# SAS_UFL_Adapter.net
KiCad netlist of a schematic drawn in Altium Designer
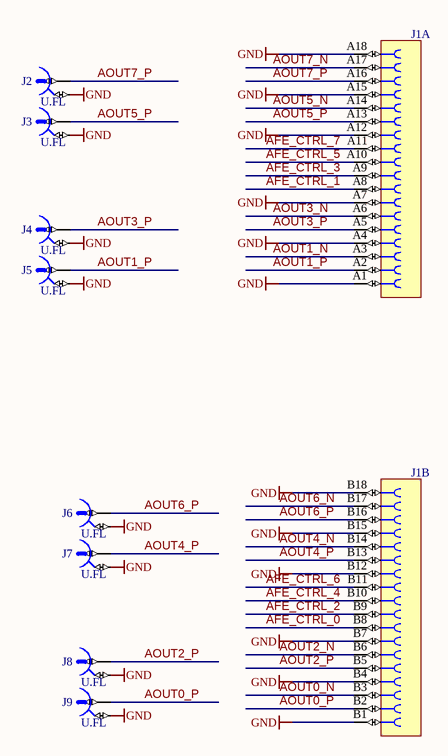
[diagram p0: SAS_UFL_Adapter.SchDoc]

(export (version "E")
  (design (tool "Eeschema 10.0.6"))
  (components
    (comp (ref "J1")
      (value "mini-SAS")
      (footprint "mini_SAS_PCB_EDGE")
      (description "36 Position mini-SAS PCB Edge Connector 36 (2x18)")
      (fields
        (field (name "PART NUMBER") "mini_SAS_PCB_EDGE")
        (field (name "MANUFACTURER") "PCB")
        (field (name "AUTHOR") "GK")
      )
      (libsource (lib "Connectors") (part "CON_mini_SAS_PCB_EDGE"))
    )
    (comp (ref "J2")
      (value "U.FL")
      (footprint "HIROSE_U.FL-R-SMT-1(10)")
      (fields
        (field (name "PART NUMBER") "HIROSE_U.FL-R-SMT-1(10)")
        (field (name "MANUFACTURER") "HIROSE (HRS)")
        (field (name "MANUFACTURER PART NUMBER") "U.FL-R-SMT-1(10)")
        (field (name "AUTHOR") "CERN DEM JLC")
      )
      (libsource (lib "Connectors") (part "Coax_1Male_1Shield"))
    )
    (comp (ref "J3")
      (value "U.FL")
      (footprint "HIROSE_U.FL-R-SMT-1(10)")
      (fields
        (field (name "PART NUMBER") "HIROSE_U.FL-R-SMT-1(10)")
        (field (name "MANUFACTURER") "HIROSE (HRS)")
        (field (name "MANUFACTURER PART NUMBER") "U.FL-R-SMT-1(10)")
        (field (name "AUTHOR") "CERN DEM JLC")
      )
      (libsource (lib "Connectors") (part "Coax_1Male_1Shield"))
    )
    (comp (ref "J4")
      (value "U.FL")
      (footprint "HIROSE_U.FL-R-SMT-1(10)")
      (fields
        (field (name "PART NUMBER") "HIROSE_U.FL-R-SMT-1(10)")
        (field (name "MANUFACTURER") "HIROSE (HRS)")
        (field (name "MANUFACTURER PART NUMBER") "U.FL-R-SMT-1(10)")
        (field (name "AUTHOR") "CERN DEM JLC")
      )
      (libsource (lib "Connectors") (part "Coax_1Male_1Shield"))
    )
    (comp (ref "J5")
      (value "U.FL")
      (footprint "HIROSE_U.FL-R-SMT-1(10)")
      (fields
        (field (name "PART NUMBER") "HIROSE_U.FL-R-SMT-1(10)")
        (field (name "MANUFACTURER") "HIROSE (HRS)")
        (field (name "MANUFACTURER PART NUMBER") "U.FL-R-SMT-1(10)")
        (field (name "AUTHOR") "CERN DEM JLC")
      )
      (libsource (lib "Connectors") (part "Coax_1Male_1Shield"))
    )
    (comp (ref "J6")
      (value "U.FL")
      (footprint "HIROSE_U.FL-R-SMT-1(10)")
      (fields
        (field (name "PART NUMBER") "HIROSE_U.FL-R-SMT-1(10)")
        (field (name "MANUFACTURER") "HIROSE (HRS)")
        (field (name "MANUFACTURER PART NUMBER") "U.FL-R-SMT-1(10)")
        (field (name "AUTHOR") "CERN DEM JLC")
      )
      (libsource (lib "Connectors") (part "Coax_1Male_1Shield"))
    )
    (comp (ref "J7")
      (value "U.FL")
      (footprint "HIROSE_U.FL-R-SMT-1(10)")
      (fields
        (field (name "PART NUMBER") "HIROSE_U.FL-R-SMT-1(10)")
        (field (name "MANUFACTURER") "HIROSE (HRS)")
        (field (name "MANUFACTURER PART NUMBER") "U.FL-R-SMT-1(10)")
        (field (name "AUTHOR") "CERN DEM JLC")
      )
      (libsource (lib "Connectors") (part "Coax_1Male_1Shield"))
    )
    (comp (ref "J8")
      (value "U.FL")
      (footprint "HIROSE_U.FL-R-SMT-1(10)")
      (fields
        (field (name "PART NUMBER") "HIROSE_U.FL-R-SMT-1(10)")
        (field (name "MANUFACTURER") "HIROSE (HRS)")
        (field (name "MANUFACTURER PART NUMBER") "U.FL-R-SMT-1(10)")
        (field (name "AUTHOR") "CERN DEM JLC")
      )
      (libsource (lib "Connectors") (part "Coax_1Male_1Shield"))
    )
    (comp (ref "J9")
      (value "U.FL")
      (footprint "HIROSE_U.FL-R-SMT-1(10)")
      (fields
        (field (name "PART NUMBER") "HIROSE_U.FL-R-SMT-1(10)")
        (field (name "MANUFACTURER") "HIROSE (HRS)")
        (field (name "MANUFACTURER PART NUMBER") "U.FL-R-SMT-1(10)")
        (field (name "AUTHOR") "CERN DEM JLC")
      )
      (libsource (lib "Connectors") (part "Coax_1Male_1Shield"))
    )
  )
  (nets
    (net (code "1") (name "/AFE_CTRL_0") (class "Default")
      (node (ref "J1") (pin "B8") (pinfunction "B8_B8") (pintype "bidirectional"))
    )
    (net (code "2") (name "/AFE_CTRL_1") (class "Default")
      (node (ref "J1") (pin "A8") (pinfunction "A8_A8") (pintype "bidirectional"))
    )
    (net (code "3") (name "/AFE_CTRL_2") (class "Default")
      (node (ref "J1") (pin "B9") (pinfunction "B9_B9") (pintype "bidirectional"))
    )
    (net (code "4") (name "/AFE_CTRL_3") (class "Default")
      (node (ref "J1") (pin "A9") (pinfunction "A9_A9") (pintype "bidirectional"))
    )
    (net (code "5") (name "/AFE_CTRL_4") (class "Default")
      (node (ref "J1") (pin "B10") (pinfunction "B10_B10") (pintype "bidirectional"))
    )
    (net (code "6") (name "/AFE_CTRL_5") (class "Default")
      (node (ref "J1") (pin "A10") (pinfunction "A10_A10") (pintype "bidirectional"))
    )
    (net (code "7") (name "/AFE_CTRL_6") (class "Default")
      (node (ref "J1") (pin "B11") (pinfunction "B11_B11") (pintype "bidirectional"))
    )
    (net (code "8") (name "/AFE_CTRL_7") (class "Default")
      (node (ref "J1") (pin "A11") (pinfunction "A11_A11") (pintype "bidirectional"))
    )
    (net (code "9") (name "/AOUT0_N") (class "Default")
      (node (ref "J1") (pin "B3") (pinfunction "B3_B3") (pintype "bidirectional"))
    )
    (net (code "10") (name "/AOUT0_P") (class "Default")
      (node (ref "J1") (pin "B2") (pinfunction "B2_B2") (pintype "bidirectional"))
      (node (ref "J9") (pin "1") (pinfunction "1_1") (pintype "bidirectional"))
    )
    (net (code "11") (name "/AOUT1_N") (class "Default")
      (node (ref "J1") (pin "A3") (pinfunction "A3_A3") (pintype "bidirectional"))
    )
    (net (code "12") (name "/AOUT1_P") (class "Default")
      (node (ref "J1") (pin "A2") (pinfunction "A2_A2") (pintype "bidirectional"))
      (node (ref "J5") (pin "1") (pinfunction "1_1") (pintype "bidirectional"))
    )
    (net (code "13") (name "/AOUT2_N") (class "Default")
      (node (ref "J1") (pin "B6") (pinfunction "B6_B6") (pintype "bidirectional"))
    )
    (net (code "14") (name "/AOUT2_P") (class "Default")
      (node (ref "J1") (pin "B5") (pinfunction "B5_B5") (pintype "bidirectional"))
      (node (ref "J8") (pin "1") (pinfunction "1_1") (pintype "bidirectional"))
    )
    (net (code "15") (name "/AOUT3_N") (class "Default")
      (node (ref "J1") (pin "A6") (pinfunction "A6_A6") (pintype "bidirectional"))
    )
    (net (code "16") (name "/AOUT3_P") (class "Default")
      (node (ref "J1") (pin "A5") (pinfunction "A5_A5") (pintype "bidirectional"))
      (node (ref "J4") (pin "1") (pinfunction "1_1") (pintype "bidirectional"))
    )
    (net (code "17") (name "/AOUT4_N") (class "Default")
      (node (ref "J1") (pin "B14") (pinfunction "B14_B14") (pintype "bidirectional"))
    )
    (net (code "18") (name "/AOUT4_P") (class "Default")
      (node (ref "J1") (pin "B13") (pinfunction "B13_B13") (pintype "bidirectional"))
      (node (ref "J7") (pin "1") (pinfunction "1_1") (pintype "bidirectional"))
    )
    (net (code "19") (name "/AOUT5_N") (class "Default")
      (node (ref "J1") (pin "A14") (pinfunction "A14_A14") (pintype "bidirectional"))
    )
    (net (code "20") (name "/AOUT5_P") (class "Default")
      (node (ref "J1") (pin "A13") (pinfunction "A13_A13") (pintype "bidirectional"))
      (node (ref "J3") (pin "1") (pinfunction "1_1") (pintype "bidirectional"))
    )
    (net (code "21") (name "/AOUT6_N") (class "Default")
      (node (ref "J1") (pin "B17") (pinfunction "B17_B17") (pintype "bidirectional"))
    )
    (net (code "22") (name "/AOUT6_P") (class "Default")
      (node (ref "J1") (pin "B16") (pinfunction "B16_B16") (pintype "bidirectional"))
      (node (ref "J6") (pin "1") (pinfunction "1_1") (pintype "bidirectional"))
    )
    (net (code "23") (name "/AOUT7_N") (class "Default")
      (node (ref "J1") (pin "A17") (pinfunction "A17_A17") (pintype "bidirectional"))
    )
    (net (code "24") (name "/AOUT7_P") (class "Default")
      (node (ref "J1") (pin "A16") (pinfunction "A16_A16") (pintype "bidirectional"))
      (node (ref "J2") (pin "1") (pinfunction "1_1") (pintype "bidirectional"))
    )
    (net (code "25") (name "GND") (class "Default")
      (node (ref "J1") (pin "A1") (pinfunction "A1_A1") (pintype "bidirectional"))
      (node (ref "J1") (pin "A12") (pinfunction "A12_A12") (pintype "bidirectional"))
      (node (ref "J1") (pin "A15") (pinfunction "A15_A15") (pintype "bidirectional"))
      (node (ref "J1") (pin "A18") (pinfunction "A18_A18") (pintype "bidirectional"))
      (node (ref "J1") (pin "A4") (pinfunction "A4_A4") (pintype "bidirectional"))
      (node (ref "J1") (pin "A7") (pinfunction "A7_A7") (pintype "bidirectional"))
      (node (ref "J1") (pin "B1") (pinfunction "B1_B1") (pintype "bidirectional"))
      (node (ref "J1") (pin "B12") (pinfunction "B12_B12") (pintype "bidirectional"))
      (node (ref "J1") (pin "B15") (pinfunction "B15_B15") (pintype "bidirectional"))
      (node (ref "J1") (pin "B18") (pinfunction "B18_B18") (pintype "bidirectional"))
      (node (ref "J1") (pin "B4") (pinfunction "B4_B4") (pintype "bidirectional"))
      (node (ref "J1") (pin "B7") (pinfunction "B7_B7") (pintype "bidirectional"))
      (node (ref "J2") (pin "2") (pinfunction "2_2") (pintype "bidirectional"))
      (node (ref "J3") (pin "2") (pinfunction "2_2") (pintype "bidirectional"))
      (node (ref "J4") (pin "2") (pinfunction "2_2") (pintype "bidirectional"))
      (node (ref "J5") (pin "2") (pinfunction "2_2") (pintype "bidirectional"))
      (node (ref "J6") (pin "2") (pinfunction "2_2") (pintype "bidirectional"))
      (node (ref "J7") (pin "2") (pinfunction "2_2") (pintype "bidirectional"))
      (node (ref "J8") (pin "2") (pinfunction "2_2") (pintype "bidirectional"))
      (node (ref "J9") (pin "2") (pinfunction "2_2") (pintype "bidirectional"))
    )
  )
)
